# minisumo_sensor.net
KiCad netlist of a schematic drawn in EAGLE
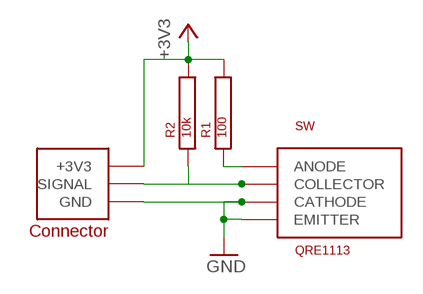
[diagram p0: schematic, sheet 1]

(export (version "E")
  (design (tool "Eeschema 10.0.6"))
  (components
    (comp (ref "R1")
      (value "100")
      (footprint "eagle-import:RES_0402")
      (libsource (lib "eagle-import") (part "RESISTOR"))
    )
    (comp (ref "R2")
      (value "10k")
      (footprint "eagle-import:RES_0402")
      (libsource (lib "eagle-import") (part "RESISTOR"))
    )
    (comp (ref "SW")
      (value "QRE1113")
      (footprint "eagle-import:QRE1113")
      (libsource (lib "eagle-import") (part "QRE1113"))
    )
    (comp (ref "U$1")
      (value "QRE1113_CONNECTOR")
      (footprint "eagle-import:QRE1113_CONNECTOR")
      (libsource (lib "eagle-import") (part "QRE1113_CONNECTOR"))
    )
  )
  (nets
    (net (code "1") (name "+3V3") (class "Default")
      (node (ref "R1") (pin "P$2") (pinfunction "P$2_P$2") (pintype "bidirectional"))
      (node (ref "R2") (pin "P$2") (pinfunction "P$2_P$2") (pintype "bidirectional"))
      (node (ref "U$1") (pin "+3V3") (pinfunction "+3V3_+3V3") (pintype "bidirectional"))
    )
    (net (code "2") (name "GND") (class "Default")
      (node (ref "SW") (pin "CATHODE") (pinfunction "CATHODE_CATHODE") (pintype "bidirectional"))
      (node (ref "SW") (pin "EMITTER") (pinfunction "EMITTER_EMITTER") (pintype "bidirectional"))
      (node (ref "U$1") (pin "GND") (pinfunction "GND_GND") (pintype "bidirectional"))
    )
    (net (code "3") (name "Net-(R1-PadP$1)") (class "Default")
      (node (ref "R1") (pin "P$1") (pinfunction "P$1_P$1") (pintype "bidirectional"))
      (node (ref "SW") (pin "ANODE") (pinfunction "ANODE_ANODE") (pintype "bidirectional"))
    )
    (net (code "4") (name "Net-(R2-PadP$1)") (class "Default")
      (node (ref "R2") (pin "P$1") (pinfunction "P$1_P$1") (pintype "bidirectional"))
      (node (ref "SW") (pin "COLLECTOR") (pinfunction "COLLECTOR_COLLECTOR") (pintype "bidirectional"))
      (node (ref "U$1") (pin "SIGNAL") (pinfunction "SIGNAL_SIGNAL") (pintype "bidirectional"))
    )
  )
)
